# DRV8833.net
KiCad netlist of a schematic drawn in EAGLE
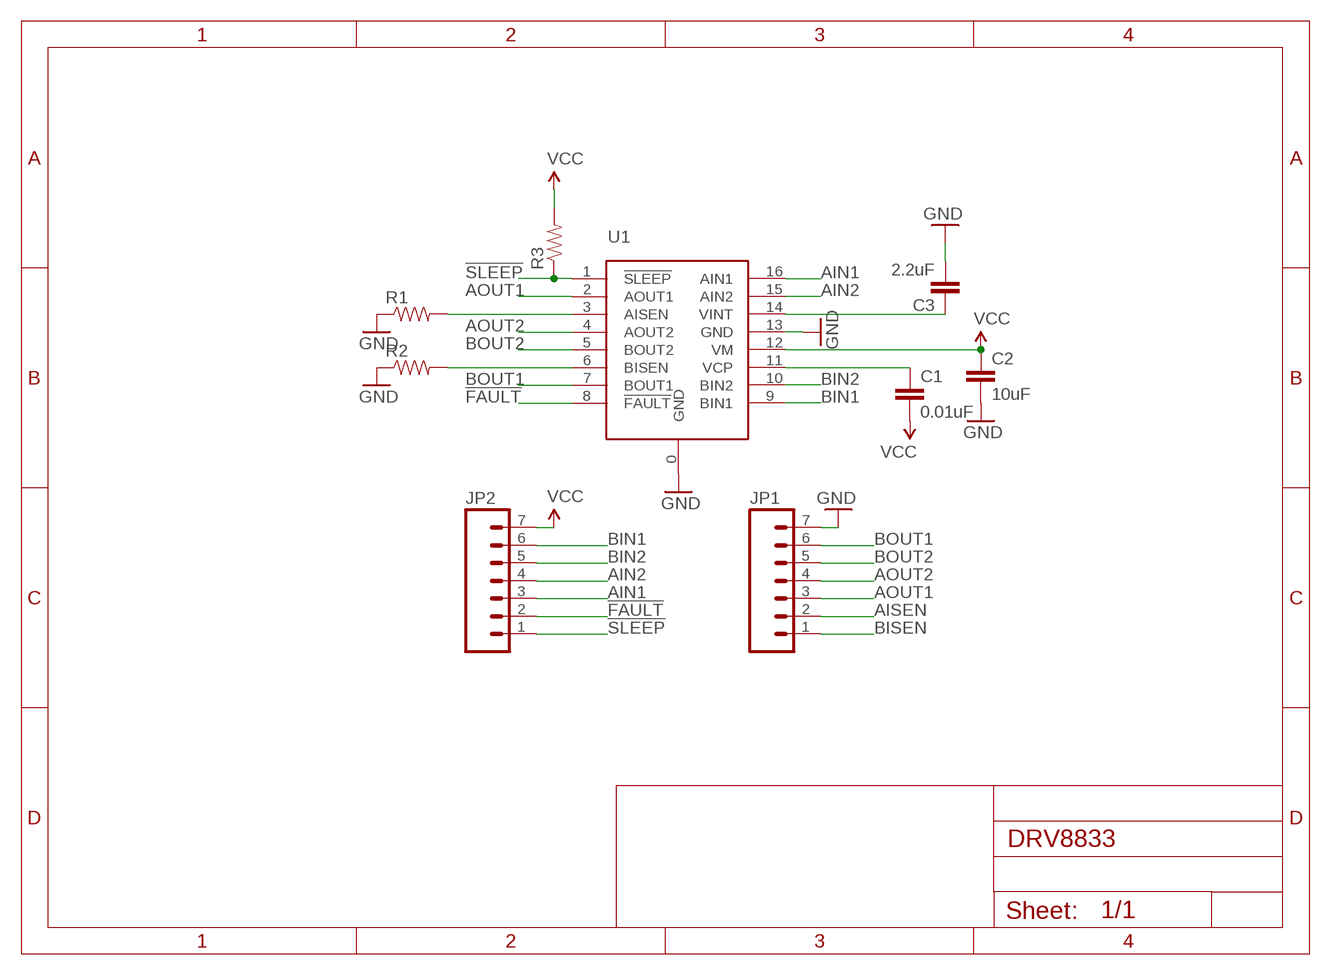
[diagram p0: schematic, sheet 1]

(export (version "E")
  (design (tool "Eeschema 10.0.6"))
  (components
    (comp (ref "C1")
      (value "0.01uF")
      (footprint "eagle-import:0603-CAP")
      (libsource (lib "eagle-import") (part "CAP0603-CAP"))
    )
    (comp (ref "C2")
      (value "10uF")
      (footprint "eagle-import:1206")
      (libsource (lib "eagle-import") (part "CAP1206"))
    )
    (comp (ref "C3")
      (value "2.2uF")
      (footprint "eagle-import:0603-CAP")
      (libsource (lib "eagle-import") (part "CAP0603-CAP"))
    )
    (comp (ref "JP1")
      (value "M07")
      (footprint "eagle-import:1X07")
      (libsource (lib "eagle-import") (part "M07"))
    )
    (comp (ref "JP2")
      (value "M07")
      (footprint "eagle-import:1X07")
      (libsource (lib "eagle-import") (part "M07"))
    )
    (comp (ref "R1")
      (value "RESISTOR1206")
      (footprint "eagle-import:1206")
      (libsource (lib "eagle-import") (part "RESISTOR1206"))
    )
    (comp (ref "R2")
      (value "RESISTOR1206")
      (footprint "eagle-import:1206")
      (libsource (lib "eagle-import") (part "RESISTOR1206"))
    )
    (comp (ref "R3")
      (value "RESISTOR0603-RES")
      (footprint "eagle-import:0603-RES")
      (libsource (lib "eagle-import") (part "RESISTOR0603-RES"))
    )
    (comp (ref "U1")
      (value "DRV8833")
      (footprint "eagle-import:PWP16")
      (libsource (lib "eagle-import") (part "DRV8833"))
    )
  )
  (nets
    (net (code "1") (name "/AIN1") (class "Default")
      (node (ref "JP2") (pin "3") (pinfunction "3_3") (pintype "passive"))
      (node (ref "U1") (pin "16") (pinfunction "AIN1_16") (pintype "bidirectional"))
    )
    (net (code "2") (name "/AIN2") (class "Default")
      (node (ref "JP2") (pin "4") (pinfunction "4_4") (pintype "passive"))
      (node (ref "U1") (pin "15") (pinfunction "AIN2_15") (pintype "bidirectional"))
    )
    (net (code "3") (name "/AISEN") (class "Default")
      (node (ref "JP1") (pin "2") (pinfunction "2_2") (pintype "passive"))
      (node (ref "R1") (pin "2") (pinfunction "2_2") (pintype "passive"))
      (node (ref "U1") (pin "3") (pinfunction "AISEN_3") (pintype "bidirectional"))
    )
    (net (code "4") (name "/AOUT1") (class "Default")
      (node (ref "JP1") (pin "3") (pinfunction "3_3") (pintype "passive"))
      (node (ref "U1") (pin "2") (pinfunction "AOUT1_2") (pintype "bidirectional"))
    )
    (net (code "5") (name "/AOUT2") (class "Default")
      (node (ref "JP1") (pin "4") (pinfunction "4_4") (pintype "passive"))
      (node (ref "U1") (pin "4") (pinfunction "AOUT2_4") (pintype "bidirectional"))
    )
    (net (code "6") (name "/BIN1") (class "Default")
      (node (ref "JP2") (pin "6") (pinfunction "6_6") (pintype "passive"))
      (node (ref "U1") (pin "9") (pinfunction "BIN1_9") (pintype "bidirectional"))
    )
    (net (code "7") (name "/BIN2") (class "Default")
      (node (ref "JP2") (pin "5") (pinfunction "5_5") (pintype "passive"))
      (node (ref "U1") (pin "10") (pinfunction "BIN2_10") (pintype "bidirectional"))
    )
    (net (code "8") (name "/BISEN") (class "Default")
      (node (ref "JP1") (pin "1") (pinfunction "1_1") (pintype "passive"))
      (node (ref "R2") (pin "2") (pinfunction "2_2") (pintype "passive"))
      (node (ref "U1") (pin "6") (pinfunction "BISEN_6") (pintype "bidirectional"))
    )
    (net (code "9") (name "/BOUT1") (class "Default")
      (node (ref "JP1") (pin "6") (pinfunction "6_6") (pintype "passive"))
      (node (ref "U1") (pin "7") (pinfunction "BOUT1_7") (pintype "bidirectional"))
    )
    (net (code "10") (name "/BOUT2") (class "Default")
      (node (ref "JP1") (pin "5") (pinfunction "5_5") (pintype "passive"))
      (node (ref "U1") (pin "5") (pinfunction "BOUT2_5") (pintype "bidirectional"))
    )
    (net (code "11") (name "/~{FAULT}") (class "Default")
      (node (ref "JP2") (pin "2") (pinfunction "2_2") (pintype "passive"))
      (node (ref "U1") (pin "8") (pinfunction "~{FAULT}_8") (pintype "bidirectional"))
    )
    (net (code "12") (name "/~{SLEEP}") (class "Default")
      (node (ref "JP2") (pin "1") (pinfunction "1_1") (pintype "passive"))
      (node (ref "R3") (pin "1") (pinfunction "1_1") (pintype "passive"))
      (node (ref "U1") (pin "1") (pinfunction "~{SLEEP}_1") (pintype "bidirectional"))
    )
    (net (code "13") (name "GND") (class "Default")
      (node (ref "C2") (pin "2") (pinfunction "2_2") (pintype "passive"))
      (node (ref "C3") (pin "2") (pinfunction "2_2") (pintype "passive"))
      (node (ref "JP1") (pin "7") (pinfunction "7_7") (pintype "passive"))
      (node (ref "R1") (pin "1") (pinfunction "1_1") (pintype "passive"))
      (node (ref "R2") (pin "1") (pinfunction "1_1") (pintype "passive"))
      (node (ref "U1") (pin "0") (pinfunction "GND_0") (pintype "bidirectional"))
      (node (ref "U1") (pin "13") (pinfunction "GND_13") (pintype "bidirectional"))
    )
    (net (code "14") (name "Net-(U1-VCP)") (class "Default")
      (node (ref "C1") (pin "1") (pinfunction "1_1") (pintype "passive"))
      (node (ref "U1") (pin "11") (pinfunction "VCP_11") (pintype "bidirectional"))
    )
    (net (code "15") (name "Net-(U1-VINT)") (class "Default")
      (node (ref "C3") (pin "1") (pinfunction "1_1") (pintype "passive"))
      (node (ref "U1") (pin "14") (pinfunction "VINT_14") (pintype "bidirectional"))
    )
    (net (code "16") (name "VCC") (class "Default")
      (node (ref "C1") (pin "2") (pinfunction "2_2") (pintype "passive"))
      (node (ref "C2") (pin "1") (pinfunction "1_1") (pintype "passive"))
      (node (ref "JP2") (pin "7") (pinfunction "7_7") (pintype "passive"))
      (node (ref "R3") (pin "2") (pinfunction "2_2") (pintype "passive"))
      (node (ref "U1") (pin "12") (pinfunction "VM_12") (pintype "bidirectional"))
    )
  )
)
